# 780-00012-P1_rev4_Sch_M2_Focus_Drive.net
KiCad netlist of a schematic drawn in Altium Designer
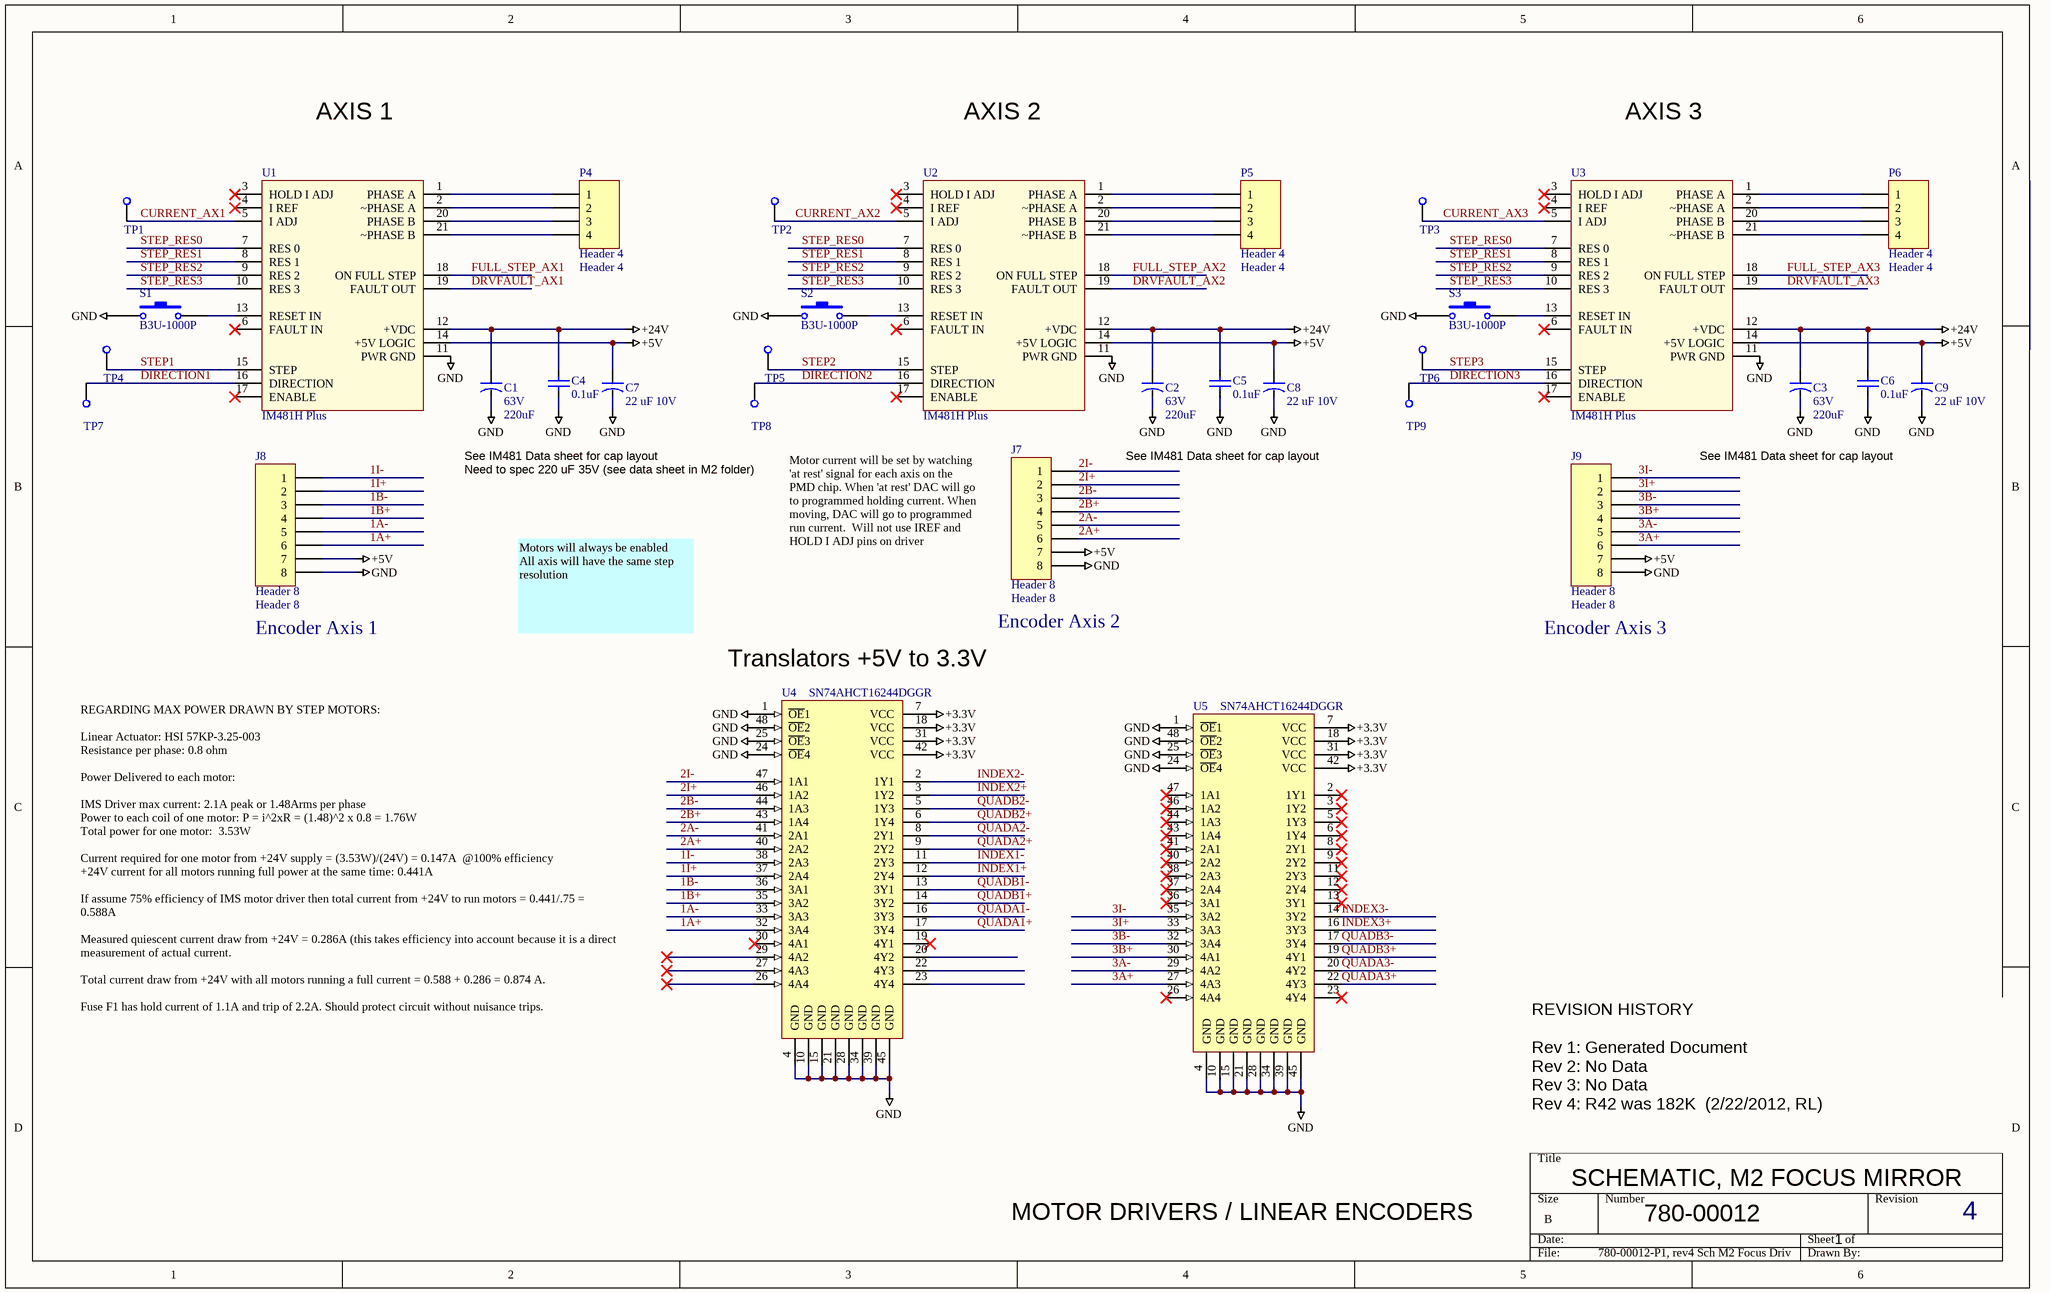
[diagram p0: 780-00012-P1, rev4 Sch M2 Focus Drive.SchDoc]

(export (version "E")
  (design (tool "Eeschema 10.0.6"))
  (components
    (comp (ref "C1")
      (value "63V")
      (footprint "CAP 220uF 63V")
      (description "CAP 220UF 63V ELECT MVH SMD")
      (fields (field (name "MANUFACTURER") "United Chemi-Con") (field (name "ALTIUM_VALUE") "220uF"))
      (libsource (lib "Richs Schematic Components") (part "Cap 220uF, 63V"))
    )
    (comp (ref "C2")
      (value "63V")
      (footprint "CAP 220uF 63V")
      (description "CAP 220UF 63V ELECT MVH SMD")
      (fields (field (name "MANUFACTURER") "United Chemi-Con") (field (name "ALTIUM_VALUE") "220uF"))
      (libsource (lib "Richs Schematic Components") (part "Cap 220uF, 63V"))
    )
    (comp (ref "C3")
      (value "63V")
      (footprint "CAP 220uF 63V")
      (description "CAP 220UF 63V ELECT MVH SMD")
      (fields (field (name "MANUFACTURER") "United Chemi-Con") (field (name "ALTIUM_VALUE") "220uF"))
      (libsource (lib "Richs Schematic Components") (part "Cap 220uF, 63V"))
    )
    (comp (ref "C4")
      (value "0.1uF")
      (footprint "SMD_0805")
      (description "Capacitor")
      (fields (field (name "Comment") "Cap SMD"))
      (libsource (lib "Richs Schematic Components") (part "Cap SMD"))
    )
    (comp (ref "C5")
      (value "0.1uF")
      (footprint "SMD_0805")
      (description "Capacitor")
      (fields (field (name "Comment") "Cap SMD"))
      (libsource (lib "Richs Schematic Components") (part "Cap SMD"))
    )
    (comp (ref "C6")
      (value "0.1uF")
      (footprint "SMD_0805")
      (description "Capacitor")
      (fields (field (name "Comment") "Cap SMD"))
      (libsource (lib "Richs Schematic Components") (part "Cap SMD"))
    )
    (comp (ref "C7")
      (value "22 uF 10V")
      (footprint "SMD_CAP_3216")
      (description "outline 3.2mm x 1.6mm")
      (fields (field (name "MANUFACTURER") "KEMET") (field (name "Comment") "16V"))
      (libsource (lib "Richs Schematic Components") (part "Cap Tant 16V"))
    )
    (comp (ref "C8")
      (value "22 uF 10V")
      (footprint "SMD_CAP_3216")
      (description "outline 3.2mm x 1.6mm")
      (fields (field (name "MANUFACTURER") "KEMET") (field (name "Comment") "16V"))
      (libsource (lib "Richs Schematic Components") (part "Cap Tant 16V"))
    )
    (comp (ref "C9")
      (value "22 uF 10V")
      (footprint "SMD_CAP_3216")
      (description "outline 3.2mm x 1.6mm")
      (fields (field (name "MANUFACTURER") "KEMET") (field (name "Comment") "16V"))
      (libsource (lib "Richs Schematic Components") (part "Cap Tant 16V"))
    )
    (comp (ref "J7")
      (value "Header 8")
      (footprint "HDR1X8 for IDC")
      (description "Header, 8-Pin")
      (fields (field (name "ALTIUM_VALUE") "Header 8"))
      (libsource (lib "Richs Schematic Components") (part "Header 8"))
    )
    (comp (ref "J8")
      (value "Header 8")
      (footprint "HDR1X8 for IDC")
      (description "Header, 8-Pin")
      (fields (field (name "ALTIUM_VALUE") "Header 8"))
      (libsource (lib "Richs Schematic Components") (part "Header 8"))
    )
    (comp (ref "J9")
      (value "Header 8")
      (footprint "HDR1X8 for IDC")
      (description "Header, 8-Pin")
      (fields (field (name "ALTIUM_VALUE") "Header 8"))
      (libsource (lib "Richs Schematic Components") (part "Header 8"))
    )
    (comp (ref "P4")
      (value "Header 4")
      (footprint "HDR1X4 for IDC")
      (description "Header, 4-Pin")
      (fields (field (name "ALTIUM_VALUE") "Header 4"))
      (libsource (lib "Richs Schematic Components") (part "Header 4"))
    )
    (comp (ref "P5")
      (value "Header 4")
      (footprint "HDR1X4 for IDC")
      (description "Header, 4-Pin")
      (fields (field (name "ALTIUM_VALUE") "Header 4"))
      (libsource (lib "Richs Schematic Components") (part "Header 4"))
    )
    (comp (ref "P6")
      (value "Header 4")
      (footprint "HDR1X4 for IDC")
      (description "Header, 4-Pin")
      (fields (field (name "ALTIUM_VALUE") "Header 4"))
      (libsource (lib "Richs Schematic Components") (part "Header 4"))
    )
    (comp (ref "S1")
      (value "B3U-1000P")
      (footprint "B3U-1000P")
      (description "Switch")
      (fields (field (name "MANUFACTURER") "Omron Electronics"))
      (libsource (lib "Miscellaneous Devices") (part "SW-PB"))
    )
    (comp (ref "S2")
      (value "B3U-1000P")
      (footprint "B3U-1000P")
      (description "Switch")
      (fields (field (name "MANUFACTURER") "Omron Electronics"))
      (libsource (lib "Miscellaneous Devices") (part "SW-PB"))
    )
    (comp (ref "S3")
      (value "B3U-1000P")
      (footprint "B3U-1000P")
      (description "Switch")
      (fields (field (name "MANUFACTURER") "Omron Electronics"))
      (libsource (lib "Miscellaneous Devices") (part "SW-PB"))
    )
    (comp (ref "TP1")
      (value "Test Point SMD")
      (footprint "SMD_TEST POINT")
      (description "SMD loop test point")
      (libsource (lib "Richs Schematic Components") (part "Test Point SMD"))
    )
    (comp (ref "TP2")
      (value "Test Point SMD")
      (footprint "SMD_TEST POINT")
      (description "SMD loop test point")
      (libsource (lib "Richs Schematic Components") (part "Test Point SMD"))
    )
    (comp (ref "TP3")
      (value "Test Point SMD")
      (footprint "SMD_TEST POINT")
      (description "SMD loop test point")
      (libsource (lib "Richs Schematic Components") (part "Test Point SMD"))
    )
    (comp (ref "TP4")
      (value "Test Point SMD")
      (footprint "SMD_TEST POINT")
      (description "SMD loop test point")
      (libsource (lib "Richs Schematic Components") (part "Test Point SMD"))
    )
    (comp (ref "TP5")
      (value "Test Point SMD")
      (footprint "SMD_TEST POINT")
      (description "SMD loop test point")
      (libsource (lib "Richs Schematic Components") (part "Test Point SMD"))
    )
    (comp (ref "TP6")
      (value "Test Point SMD")
      (footprint "SMD_TEST POINT")
      (description "SMD loop test point")
      (libsource (lib "Richs Schematic Components") (part "Test Point SMD"))
    )
    (comp (ref "TP7")
      (value "Test Point SMD")
      (footprint "SMD_TEST POINT")
      (description "SMD loop test point")
      (libsource (lib "Richs Schematic Components") (part "Test Point SMD"))
    )
    (comp (ref "TP8")
      (value "Test Point SMD")
      (footprint "SMD_TEST POINT")
      (description "SMD loop test point")
      (libsource (lib "Richs Schematic Components") (part "Test Point SMD"))
    )
    (comp (ref "TP9")
      (value "Test Point SMD")
      (footprint "SMD_TEST POINT")
      (description "SMD loop test point")
      (libsource (lib "Richs Schematic Components") (part "Test Point SMD"))
    )
    (comp (ref "U1")
      (value "IM481H Plus")
      (footprint "IM481H Vertical")
      (description "Hybrid stepper motor driver")
      (libsource (lib "Richs Schematic Components") (part "IM481H Plus"))
    )
    (comp (ref "U2")
      (value "IM481H Plus")
      (footprint "IM481H Vertical")
      (description "Hybrid stepper motor driver")
      (libsource (lib "Richs Schematic Components") (part "IM481H Plus"))
    )
    (comp (ref "U3")
      (value "IM481H Plus")
      (footprint "IM481H Vertical")
      (description "Hybrid stepper motor driver")
      (libsource (lib "Richs Schematic Components") (part "IM481H Plus"))
    )
    (comp (ref "U4")
      (value "SN74AHCT16244DGGR")
      (footprint "DGG048_N")
      (description "16-Bit Buffer/Driver with 3-State Outputs")
      (libsource (lib "TI Logic Buffer Line Driver") (part "SN74AHCT16244DGGR"))
    )
    (comp (ref "U5")
      (value "SN74AHCT16244DGGR")
      (footprint "DGG048_N")
      (description "16-Bit Buffer/Driver with 3-State Outputs")
      (libsource (lib "TI Logic Buffer Line Driver") (part "SN74AHCT16244DGGR"))
    )
  )
  (nets
    (net (code "1") (name "+3.3V") (class "Default")
      (node (ref "U4") (pin "18") (pinfunction "VCC_18") (pintype "power_in"))
      (node (ref "U4") (pin "31") (pinfunction "VCC_31") (pintype "power_in"))
      (node (ref "U4") (pin "42") (pinfunction "VCC_42") (pintype "power_in"))
      (node (ref "U4") (pin "7") (pinfunction "VCC_7") (pintype "power_in"))
      (node (ref "U5") (pin "18") (pinfunction "VCC_18") (pintype "power_in"))
      (node (ref "U5") (pin "31") (pinfunction "VCC_31") (pintype "power_in"))
      (node (ref "U5") (pin "42") (pinfunction "VCC_42") (pintype "power_in"))
      (node (ref "U5") (pin "7") (pinfunction "VCC_7") (pintype "power_in"))
    )
    (net (code "2") (name "+5V") (class "Default")
      (node (ref "C7") (pin "1") (pinfunction "1_1") (pintype "passive"))
      (node (ref "C8") (pin "1") (pinfunction "1_1") (pintype "passive"))
      (node (ref "C9") (pin "1") (pinfunction "1_1") (pintype "passive"))
      (node (ref "J7") (pin "7") (pinfunction "7_7") (pintype "passive"))
      (node (ref "J8") (pin "7") (pinfunction "7_7") (pintype "passive"))
      (node (ref "J9") (pin "7") (pinfunction "7_7") (pintype "passive"))
      (node (ref "U1") (pin "14") (pinfunction "+5V_LOGIC_14") (pintype "passive"))
      (node (ref "U2") (pin "14") (pinfunction "+5V_LOGIC_14") (pintype "passive"))
      (node (ref "U3") (pin "14") (pinfunction "+5V_LOGIC_14") (pintype "passive"))
    )
    (net (code "3") (name "+24V") (class "Default")
      (node (ref "C1") (pin "1") (pinfunction "1_1") (pintype "passive"))
      (node (ref "C2") (pin "1") (pinfunction "1_1") (pintype "passive"))
      (node (ref "C3") (pin "1") (pinfunction "1_1") (pintype "passive"))
      (node (ref "C4") (pin "2") (pinfunction "2_2") (pintype "passive"))
      (node (ref "C5") (pin "2") (pinfunction "2_2") (pintype "passive"))
      (node (ref "C6") (pin "2") (pinfunction "2_2") (pintype "passive"))
      (node (ref "U1") (pin "12") (pinfunction "+VDC_12") (pintype "passive"))
      (node (ref "U2") (pin "12") (pinfunction "+VDC_12") (pintype "passive"))
      (node (ref "U3") (pin "12") (pinfunction "+VDC_12") (pintype "passive"))
    )
    (net (code "4") (name "/1A+") (class "Default")
      (node (ref "J8") (pin "6") (pinfunction "6_6") (pintype "passive"))
      (node (ref "U4") (pin "32") (pinfunction "3A4_32") (pintype "input"))
    )
    (net (code "5") (name "/1A-") (class "Default")
      (node (ref "J8") (pin "5") (pinfunction "5_5") (pintype "passive"))
      (node (ref "U4") (pin "33") (pinfunction "3A3_33") (pintype "input"))
    )
    (net (code "6") (name "/1B+") (class "Default")
      (node (ref "J8") (pin "4") (pinfunction "4_4") (pintype "passive"))
      (node (ref "U4") (pin "35") (pinfunction "3A2_35") (pintype "input"))
    )
    (net (code "7") (name "/1B-") (class "Default")
      (node (ref "J8") (pin "3") (pinfunction "3_3") (pintype "passive"))
      (node (ref "U4") (pin "36") (pinfunction "3A1_36") (pintype "input"))
    )
    (net (code "8") (name "/1I+") (class "Default")
      (node (ref "J8") (pin "2") (pinfunction "2_2") (pintype "passive"))
      (node (ref "U4") (pin "37") (pinfunction "2A4_37") (pintype "input"))
    )
    (net (code "9") (name "/1I-") (class "Default")
      (node (ref "J8") (pin "1") (pinfunction "1_1") (pintype "passive"))
      (node (ref "U4") (pin "38") (pinfunction "2A3_38") (pintype "input"))
    )
    (net (code "10") (name "/2A+") (class "Default")
      (node (ref "J7") (pin "6") (pinfunction "6_6") (pintype "passive"))
      (node (ref "U4") (pin "40") (pinfunction "2A2_40") (pintype "input"))
    )
    (net (code "11") (name "/2A-") (class "Default")
      (node (ref "J7") (pin "5") (pinfunction "5_5") (pintype "passive"))
      (node (ref "U4") (pin "41") (pinfunction "2A1_41") (pintype "input"))
    )
    (net (code "12") (name "/2B+") (class "Default")
      (node (ref "J7") (pin "4") (pinfunction "4_4") (pintype "passive"))
      (node (ref "U4") (pin "43") (pinfunction "1A4_43") (pintype "input"))
    )
    (net (code "13") (name "/2B-") (class "Default")
      (node (ref "J7") (pin "3") (pinfunction "3_3") (pintype "passive"))
      (node (ref "U4") (pin "44") (pinfunction "1A3_44") (pintype "input"))
    )
    (net (code "14") (name "/2I+") (class "Default")
      (node (ref "J7") (pin "2") (pinfunction "2_2") (pintype "passive"))
      (node (ref "U4") (pin "46") (pinfunction "1A2_46") (pintype "input"))
    )
    (net (code "15") (name "/2I-") (class "Default")
      (node (ref "J7") (pin "1") (pinfunction "1_1") (pintype "passive"))
      (node (ref "U4") (pin "47") (pinfunction "1A1_47") (pintype "input"))
    )
    (net (code "16") (name "/3A+") (class "Default")
      (node (ref "J9") (pin "6") (pinfunction "6_6") (pintype "passive"))
      (node (ref "U5") (pin "27") (pinfunction "4A3_27") (pintype "input"))
    )
    (net (code "17") (name "/3A-") (class "Default")
      (node (ref "J9") (pin "5") (pinfunction "5_5") (pintype "passive"))
      (node (ref "U5") (pin "29") (pinfunction "4A2_29") (pintype "input"))
    )
    (net (code "18") (name "/3B+") (class "Default")
      (node (ref "J9") (pin "4") (pinfunction "4_4") (pintype "passive"))
      (node (ref "U5") (pin "30") (pinfunction "4A1_30") (pintype "input"))
    )
    (net (code "19") (name "/3B-") (class "Default")
      (node (ref "J9") (pin "3") (pinfunction "3_3") (pintype "passive"))
      (node (ref "U5") (pin "32") (pinfunction "3A4_32") (pintype "input"))
    )
    (net (code "20") (name "/3I+") (class "Default")
      (node (ref "J9") (pin "2") (pinfunction "2_2") (pintype "passive"))
      (node (ref "U5") (pin "33") (pinfunction "3A3_33") (pintype "input"))
    )
    (net (code "21") (name "/3I-") (class "Default")
      (node (ref "J9") (pin "1") (pinfunction "1_1") (pintype "passive"))
      (node (ref "U5") (pin "35") (pinfunction "3A2_35") (pintype "input"))
    )
    (net (code "22") (name "/CURRENT_AX1") (class "Default")
      (node (ref "TP1") (pin "1") (pinfunction "TP_1") (pintype "passive"))
      (node (ref "U1") (pin "5") (pinfunction "I_ADJ_5") (pintype "passive"))
    )
    (net (code "23") (name "/CURRENT_AX2") (class "Default")
      (node (ref "TP2") (pin "1") (pinfunction "TP_1") (pintype "passive"))
      (node (ref "U2") (pin "5") (pinfunction "I_ADJ_5") (pintype "passive"))
    )
    (net (code "24") (name "/CURRENT_AX3") (class "Default")
      (node (ref "TP3") (pin "1") (pinfunction "TP_1") (pintype "passive"))
      (node (ref "U3") (pin "5") (pinfunction "I_ADJ_5") (pintype "passive"))
    )
    (net (code "25") (name "/DIRECTION1") (class "Default")
      (node (ref "TP7") (pin "1") (pinfunction "TP_1") (pintype "passive"))
      (node (ref "U1") (pin "16") (pinfunction "DIRECTION_16") (pintype "passive"))
    )
    (net (code "26") (name "/DIRECTION2") (class "Default")
      (node (ref "TP8") (pin "1") (pinfunction "TP_1") (pintype "passive"))
      (node (ref "U2") (pin "16") (pinfunction "DIRECTION_16") (pintype "passive"))
    )
    (net (code "27") (name "/DIRECTION3") (class "Default")
      (node (ref "TP9") (pin "1") (pinfunction "TP_1") (pintype "passive"))
      (node (ref "U3") (pin "16") (pinfunction "DIRECTION_16") (pintype "passive"))
    )
    (net (code "28") (name "/DRVFAULT_AX1") (class "Default")
      (node (ref "U1") (pin "19") (pinfunction "FAULT_OUT_19") (pintype "passive"))
    )
    (net (code "29") (name "/DRVFAULT_AX2") (class "Default")
      (node (ref "U2") (pin "19") (pinfunction "FAULT_OUT_19") (pintype "passive"))
    )
    (net (code "30") (name "/DRVFAULT_AX3") (class "Default")
      (node (ref "U3") (pin "19") (pinfunction "FAULT_OUT_19") (pintype "passive"))
    )
    (net (code "31") (name "/FULL_STEP_AX1") (class "Default")
      (node (ref "U1") (pin "18") (pinfunction "ON_FULL_STEP_18") (pintype "passive"))
    )
    (net (code "32") (name "/FULL_STEP_AX2") (class "Default")
      (node (ref "U2") (pin "18") (pinfunction "ON_FULL_STEP_18") (pintype "passive"))
    )
    (net (code "33") (name "/FULL_STEP_AX3") (class "Default")
      (node (ref "U3") (pin "18") (pinfunction "ON_FULL_STEP_18") (pintype "passive"))
    )
    (net (code "34") (name "/INDEX1+") (class "Default")
      (node (ref "U4") (pin "12") (pinfunction "2Y4_12") (pintype "tri_state"))
    )
    (net (code "35") (name "/INDEX1-") (class "Default")
      (node (ref "U4") (pin "11") (pinfunction "2Y3_11") (pintype "tri_state"))
    )
    (net (code "36") (name "/INDEX2+") (class "Default")
      (node (ref "U4") (pin "3") (pinfunction "1Y2_3") (pintype "tri_state"))
    )
    (net (code "37") (name "/INDEX2-") (class "Default")
      (node (ref "U4") (pin "2") (pinfunction "1Y1_2") (pintype "tri_state"))
    )
    (net (code "38") (name "/INDEX3+") (class "Default")
      (node (ref "U5") (pin "16") (pinfunction "3Y3_16") (pintype "tri_state"))
    )
    (net (code "39") (name "/INDEX3-") (class "Default")
      (node (ref "U5") (pin "14") (pinfunction "3Y2_14") (pintype "tri_state"))
    )
    (net (code "40") (name "/QUADA1+") (class "Default")
      (node (ref "U4") (pin "17") (pinfunction "3Y4_17") (pintype "tri_state"))
    )
    (net (code "41") (name "/QUADA1-") (class "Default")
      (node (ref "U4") (pin "16") (pinfunction "3Y3_16") (pintype "tri_state"))
    )
    (net (code "42") (name "/QUADA2+") (class "Default")
      (node (ref "U4") (pin "9") (pinfunction "2Y2_9") (pintype "tri_state"))
    )
    (net (code "43") (name "/QUADA2-") (class "Default")
      (node (ref "U4") (pin "8") (pinfunction "2Y1_8") (pintype "tri_state"))
    )
    (net (code "44") (name "/QUADA3+") (class "Default")
      (node (ref "U5") (pin "22") (pinfunction "4Y3_22") (pintype "tri_state"))
    )
    (net (code "45") (name "/QUADA3-") (class "Default")
      (node (ref "U5") (pin "20") (pinfunction "4Y2_20") (pintype "tri_state"))
    )
    (net (code "46") (name "/QUADB1+") (class "Default")
      (node (ref "U4") (pin "14") (pinfunction "3Y2_14") (pintype "tri_state"))
    )
    (net (code "47") (name "/QUADB1-") (class "Default")
      (node (ref "U4") (pin "13") (pinfunction "3Y1_13") (pintype "tri_state"))
    )
    (net (code "48") (name "/QUADB2+") (class "Default")
      (node (ref "U4") (pin "6") (pinfunction "1Y4_6") (pintype "tri_state"))
    )
    (net (code "49") (name "/QUADB2-") (class "Default")
      (node (ref "U4") (pin "5") (pinfunction "1Y3_5") (pintype "tri_state"))
    )
    (net (code "50") (name "/QUADB3+") (class "Default")
      (node (ref "U5") (pin "19") (pinfunction "4Y1_19") (pintype "tri_state"))
    )
    (net (code "51") (name "/QUADB3-") (class "Default")
      (node (ref "U5") (pin "17") (pinfunction "3Y4_17") (pintype "tri_state"))
    )
    (net (code "52") (name "/STEP1") (class "Default")
      (node (ref "TP4") (pin "1") (pinfunction "TP_1") (pintype "passive"))
      (node (ref "U1") (pin "15") (pinfunction "STEP_15") (pintype "passive"))
    )
    (net (code "53") (name "/STEP2") (class "Default")
      (node (ref "TP5") (pin "1") (pinfunction "TP_1") (pintype "passive"))
      (node (ref "U2") (pin "15") (pinfunction "STEP_15") (pintype "passive"))
    )
    (net (code "54") (name "/STEP3") (class "Default")
      (node (ref "TP6") (pin "1") (pinfunction "TP_1") (pintype "passive"))
      (node (ref "U3") (pin "15") (pinfunction "STEP_15") (pintype "passive"))
    )
    (net (code "55") (name "/STEP_RES0") (class "Default")
      (node (ref "U1") (pin "7") (pinfunction "RES_0_7") (pintype "passive"))
      (node (ref "U2") (pin "7") (pinfunction "RES_0_7") (pintype "passive"))
      (node (ref "U3") (pin "7") (pinfunction "RES_0_7") (pintype "passive"))
    )
    (net (code "56") (name "/STEP_RES1") (class "Default")
      (node (ref "U1") (pin "8") (pinfunction "RES_1_8") (pintype "passive"))
      (node (ref "U2") (pin "8") (pinfunction "RES_1_8") (pintype "passive"))
      (node (ref "U3") (pin "8") (pinfunction "RES_1_8") (pintype "passive"))
    )
    (net (code "57") (name "/STEP_RES2") (class "Default")
      (node (ref "U1") (pin "9") (pinfunction "RES_2_9") (pintype "passive"))
      (node (ref "U2") (pin "9") (pinfunction "RES_2_9") (pintype "passive"))
      (node (ref "U3") (pin "9") (pinfunction "RES_2_9") (pintype "passive"))
    )
    (net (code "58") (name "/STEP_RES3") (class "Default")
      (node (ref "U1") (pin "10") (pinfunction "RES_3_10") (pintype "passive"))
      (node (ref "U2") (pin "10") (pinfunction "RES_3_10") (pintype "passive"))
      (node (ref "U3") (pin "10") (pinfunction "RES_3_10") (pintype "passive"))
    )
    (net (code "59") (name "GND") (class "Default")
      (node (ref "C1") (pin "2") (pinfunction "2_2") (pintype "passive"))
      (node (ref "C2") (pin "2") (pinfunction "2_2") (pintype "passive"))
      (node (ref "C3") (pin "2") (pinfunction "2_2") (pintype "passive"))
      (node (ref "C4") (pin "1") (pinfunction "1_1") (pintype "passive"))
      (node (ref "C5") (pin "1") (pinfunction "1_1") (pintype "passive"))
      (node (ref "C6") (pin "1") (pinfunction "1_1") (pintype "passive"))
      (node (ref "C7") (pin "2") (pinfunction "2_2") (pintype "passive"))
      (node (ref "C8") (pin "2") (pinfunction "2_2") (pintype "passive"))
      (node (ref "C9") (pin "2") (pinfunction "2_2") (pintype "passive"))
      (node (ref "J7") (pin "8") (pinfunction "8_8") (pintype "passive"))
      (node (ref "J8") (pin "8") (pinfunction "8_8") (pintype "passive"))
      (node (ref "J9") (pin "8") (pinfunction "8_8") (pintype "passive"))
      (node (ref "S1") (pin "1") (pinfunction "1_1") (pintype "passive"))
      (node (ref "S2") (pin "1") (pinfunction "1_1") (pintype "passive"))
      (node (ref "S3") (pin "1") (pinfunction "1_1") (pintype "passive"))
      (node (ref "U1") (pin "11") (pinfunction "PWR_GND_11") (pintype "passive"))
      (node (ref "U2") (pin "11") (pinfunction "PWR_GND_11") (pintype "passive"))
      (node (ref "U3") (pin "11") (pinfunction "PWR_GND_11") (pintype "passive"))
      (node (ref "U4") (pin "1") (pinfunction "~{OE}1_1") (pintype "input"))
      (node (ref "U4") (pin "10") (pinfunction "GND_10") (pintype "power_in"))
      (node (ref "U4") (pin "15") (pinfunction "GND_15") (pintype "power_in"))
      (node (ref "U4") (pin "21") (pinfunction "GND_21") (pintype "power_in"))
      (node (ref "U4") (pin "24") (pinfunction "~{OE}4_24") (pintype "input"))
      (node (ref "U4") (pin "25") (pinfunction "~{OE}3_25") (pintype "input"))
      (node (ref "U4") (pin "28") (pinfunction "GND_28") (pintype "power_in"))
      (node (ref "U4") (pin "34") (pinfunction "GND_34") (pintype "power_in"))
      (node (ref "U4") (pin "39") (pinfunction "GND_39") (pintype "power_in"))
      (node (ref "U4") (pin "4") (pinfunction "GND_4") (pintype "power_in"))
      (node (ref "U4") (pin "45") (pinfunction "GND_45") (pintype "power_in"))
      (node (ref "U4") (pin "48") (pinfunction "~{OE}2_48") (pintype "input"))
      (node (ref "U5") (pin "1") (pinfunction "~{OE}1_1") (pintype "input"))
      (node (ref "U5") (pin "10") (pinfunction "GND_10") (pintype "power_in"))
      (node (ref "U5") (pin "15") (pinfunction "GND_15") (pintype "power_in"))
      (node (ref "U5") (pin "21") (pinfunction "GND_21") (pintype "power_in"))
      (node (ref "U5") (pin "24") (pinfunction "~{OE}4_24") (pintype "input"))
      (node (ref "U5") (pin "25") (pinfunction "~{OE}3_25") (pintype "input"))
      (node (ref "U5") (pin "28") (pinfunction "GND_28") (pintype "power_in"))
      (node (ref "U5") (pin "34") (pinfunction "GND_34") (pintype "power_in"))
      (node (ref "U5") (pin "39") (pinfunction "GND_39") (pintype "power_in"))
      (node (ref "U5") (pin "4") (pinfunction "GND_4") (pintype "power_in"))
      (node (ref "U5") (pin "45") (pinfunction "GND_45") (pintype "power_in"))
      (node (ref "U5") (pin "48") (pinfunction "~{OE}2_48") (pintype "input"))
    )
    (net (code "60") (name "Net-(U1-PHASE_A)") (class "Default")
      (node (ref "P4") (pin "1") (pinfunction "1_1") (pintype "passive"))
      (node (ref "U1") (pin "1") (pinfunction "PHASE_A_1") (pintype "passive"))
    )
    (net (code "61") (name "Net-(U1-PHASE_B)") (class "Default")
      (node (ref "P4") (pin "3") (pinfunction "3_3") (pintype "passive"))
      (node (ref "U1") (pin "20") (pinfunction "PHASE_B_20") (pintype "passive"))
    )
    (net (code "62") (name "Net-(U1-RESET_IN)") (class "Default")
      (node (ref "S1") (pin "2") (pinfunction "2_2") (pintype "passive"))
      (node (ref "U1") (pin "13") (pinfunction "RESET_IN_13") (pintype "passive"))
    )
    (net (code "63") (name "Net-(U1-~PHASE_A)") (class "Default")
      (node (ref "P4") (pin "2") (pinfunction "2_2") (pintype "passive"))
      (node (ref "U1") (pin "2") (pinfunction "~PHASE_A_2") (pintype "passive"))
    )
    (net (code "64") (name "Net-(U1-~PHASE_B)") (class "Default")
      (node (ref "P4") (pin "4") (pinfunction "4_4") (pintype "passive"))
      (node (ref "U1") (pin "21") (pinfunction "~PHASE_B_21") (pintype "passive"))
    )
    (net (code "65") (name "Net-(U2-PHASE_A)") (class "Default")
      (node (ref "P5") (pin "1") (pinfunction "1_1") (pintype "passive"))
      (node (ref "U2") (pin "1") (pinfunction "PHASE_A_1") (pintype "passive"))
    )
    (net (code "66") (name "Net-(U2-PHASE_B)") (class "Default")
      (node (ref "P5") (pin "3") (pinfunction "3_3") (pintype "passive"))
      (node (ref "U2") (pin "20") (pinfunction "PHASE_B_20") (pintype "passive"))
    )
    (net (code "67") (name "Net-(U2-RESET_IN)") (class "Default")
      (node (ref "S2") (pin "2") (pinfunction "2_2") (pintype "passive"))
      (node (ref "U2") (pin "13") (pinfunction "RESET_IN_13") (pintype "passive"))
    )
    (net (code "68") (name "Net-(U2-~PHASE_A)") (class "Default")
      (node (ref "P5") (pin "2") (pinfunction "2_2") (pintype "passive"))
      (node (ref "U2") (pin "2") (pinfunction "~PHASE_A_2") (pintype "passive"))
    )
    (net (code "69") (name "Net-(U2-~PHASE_B)") (class "Default")
      (node (ref "P5") (pin "4") (pinfunction "4_4") (pintype "passive"))
      (node (ref "U2") (pin "21") (pinfunction "~PHASE_B_21") (pintype "passive"))
    )
    (net (code "70") (name "Net-(U3-PHASE_A)") (class "Default")
      (node (ref "P6") (pin "1") (pinfunction "1_1") (pintype "passive"))
      (node (ref "U3") (pin "1") (pinfunction "PHASE_A_1") (pintype "passive"))
    )
    (net (code "71") (name "Net-(U3-PHASE_B)") (class "Default")
      (node (ref "P6") (pin "3") (pinfunction "3_3") (pintype "passive"))
      (node (ref "U3") (pin "20") (pinfunction "PHASE_B_20") (pintype "passive"))
    )
    (net (code "72") (name "Net-(U3-RESET_IN)") (class "Default")
      (node (ref "S3") (pin "2") (pinfunction "2_2") (pintype "passive"))
      (node (ref "U3") (pin "13") (pinfunction "RESET_IN_13") (pintype "passive"))
    )
    (net (code "73") (name "Net-(U3-~PHASE_A)") (class "Default")
      (node (ref "P6") (pin "2") (pinfunction "2_2") (pintype "passive"))
      (node (ref "U3") (pin "2") (pinfunction "~PHASE_A_2") (pintype "passive"))
    )
    (net (code "74") (name "Net-(U3-~PHASE_B)") (class "Default")
      (node (ref "P6") (pin "4") (pinfunction "4_4") (pintype "passive"))
      (node (ref "U3") (pin "21") (pinfunction "~PHASE_B_21") (pintype "passive"))
    )
    (net (code "75") (name "unconnected-(U1-ENABLE-Pad17)") (class "Default")
      (node (ref "U1") (pin "17") (pinfunction "ENABLE_17") (pintype "passive+no_connect"))
    )
    (net (code "76") (name "unconnected-(U1-FAULT_IN-Pad6)") (class "Default")
      (node (ref "U1") (pin "6") (pinfunction "FAULT_IN_6") (pintype "passive+no_connect"))
    )
    (net (code "77") (name "unconnected-(U1-HOLD_I_ADJ-Pad3)") (class "Default")
      (node (ref "U1") (pin "3") (pinfunction "HOLD_I_ADJ_3") (pintype "passive+no_connect"))
    )
    (net (code "78") (name "unconnected-(U1-I_REF-Pad4)") (class "Default")
      (node (ref "U1") (pin "4") (pinfunction "I_REF_4") (pintype "passive+no_connect"))
    )
    (net (code "79") (name "unconnected-(U2-ENABLE-Pad17)") (class "Default")
      (node (ref "U2") (pin "17") (pinfunction "ENABLE_17") (pintype "passive+no_connect"))
    )
    (net (code "80") (name "unconnected-(U2-FAULT_IN-Pad6)") (class "Default")
      (node (ref "U2") (pin "6") (pinfunction "FAULT_IN_6") (pintype "passive+no_connect"))
    )
    (net (code "81") (name "unconnected-(U2-HOLD_I_ADJ-Pad3)") (class "Default")
      (node (ref "U2") (pin "3") (pinfunction "HOLD_I_ADJ_3") (pintype "passive+no_connect"))
    )
    (net (code "82") (name "unconnected-(U2-I_REF-Pad4)") (class "Default")
      (node (ref "U2") (pin "4") (pinfunction "I_REF_4") (pintype "passive+no_connect"))
    )
    (net (code "83") (name "unconnected-(U3-ENABLE-Pad17)") (class "Default")
      (node (ref "U3") (pin "17") (pinfunction "ENABLE_17") (pintype "passive+no_connect"))
    )
    (net (code "84") (name "unconnected-(U3-FAULT_IN-Pad6)") (class "Default")
      (node (ref "U3") (pin "6") (pinfunction "FAULT_IN_6") (pintype "passive+no_connect"))
    )
    (net (code "85") (name "unconnected-(U3-HOLD_I_ADJ-Pad3)") (class "Default")
      (node (ref "U3") (pin "3") (pinfunction "HOLD_I_ADJ_3") (pintype "passive+no_connect"))
    )
    (net (code "86") (name "unconnected-(U3-I_REF-Pad4)") (class "Default")
      (node (ref "U3") (pin "4") (pinfunction "I_REF_4") (pintype "passive+no_connect"))
    )
    (net (code "87") (name "unconnected-(U4-4A1-Pad30)") (class "Default")
      (node (ref "U4") (pin "30") (pinfunction "4A1_30") (pintype "input+no_connect"))
    )
    (net (code "88") (name "unconnected-(U4-4A2-Pad29)") (class "Default")
      (node (ref "U4") (pin "29") (pinfunction "4A2_29") (pintype "input+no_connect"))
    )
    (net (code "89") (name "unconnected-(U4-4A3-Pad27)") (class "Default")
      (node (ref "U4") (pin "27") (pinfunction "4A3_27") (pintype "input+no_connect"))
    )
    (net (code "90") (name "unconnected-(U4-4A4-Pad26)") (class "Default")
      (node (ref "U4") (pin "26") (pinfunction "4A4_26") (pintype "input+no_connect"))
    )
    (net (code "91") (name "unconnected-(U4-4Y1-Pad19)") (class "Default")
      (node (ref "U4") (pin "19") (pinfunction "4Y1_19") (pintype "tri_state+no_connect"))
    )
    (net (code "92") (name "unconnected-(U4-4Y2-Pad20)") (class "Default")
      (node (ref "U4") (pin "20") (pinfunction "4Y2_20") (pintype "tri_state"))
    )
    (net (code "93") (name "unconnected-(U4-4Y3-Pad22)") (class "Default")
      (node (ref "U4") (pin "22") (pinfunction "4Y3_22") (pintype "tri_state"))
    )
    (net (code "94") (name "unconnected-(U4-4Y4-Pad23)") (class "Default")
      (node (ref "U4") (pin "23") (pinfunction "4Y4_23") (pintype "tri_state"))
    )
    (net (code "95") (name "unconnected-(U5-1A1-Pad47)") (class "Default")
      (node (ref "U5") (pin "47") (pinfunction "1A1_47") (pintype "input+no_connect"))
    )
    (net (code "96") (name "unconnected-(U5-1A2-Pad46)") (class "Default")
      (node (ref "U5") (pin "46") (pinfunction "1A2_46") (pintype "input+no_connect"))
    )
    (net (code "97") (name "unconnected-(U5-1A3-Pad44)") (class "Default")
      (node (ref "U5") (pin "44") (pinfunction "1A3_44") (pintype "input+no_connect"))
    )
    (net (code "98") (name "unconnected-(U5-1A4-Pad43)") (class "Default")
      (node (ref "U5") (pin "43") (pinfunction "1A4_43") (pintype "input+no_connect"))
    )
    (net (code "99") (name "unconnected-(U5-1Y1-Pad2)") (class "Default")
      (node (ref "U5") (pin "2") (pinfunction "1Y1_2") (pintype "tri_state+no_connect"))
    )
    (net (code "100") (name "unconnected-(U5-1Y2-Pad3)") (class "Default")
      (node (ref "U5") (pin "3") (pinfunction "1Y2_3") (pintype "tri_state+no_connect"))
    )
    (net (code "101") (name "unconnected-(U5-1Y3-Pad5)") (class "Default")
      (node (ref "U5") (pin "5") (pinfunction "1Y3_5") (pintype "tri_state+no_connect"))
    )
    (net (code "102") (name "unconnected-(U5-1Y4-Pad6)") (class "Default")
      (node (ref "U5") (pin "6") (pinfunction "1Y4_6") (pintype "tri_state+no_connect"))
    )
    (net (code "103") (name "unconnected-(U5-2A1-Pad41)") (class "Default")
      (node (ref "U5") (pin "41") (pinfunction "2A1_41") (pintype "input+no_connect"))
    )
    (net (code "104") (name "unconnected-(U5-2A2-Pad40)") (class "Default")
      (node (ref "U5") (pin "40") (pinfunction "2A2_40") (pintype "input+no_connect"))
    )
    (net (code "105") (name "unconnected-(U5-2A3-Pad38)") (class "Default")
      (node (ref "U5") (pin "38") (pinfunction "2A3_38") (pintype "input+no_connect"))
    )
    (net (code "106") (name "unconnected-(U5-2A4-Pad37)") (class "Default")
      (node (ref "U5") (pin "37") (pinfunction "2A4_37") (pintype "input+no_connect"))
    )
    (net (code "107") (name "unconnected-(U5-2Y1-Pad8)") (class "Default")
      (node (ref "U5") (pin "8") (pinfunction "2Y1_8") (pintype "tri_state+no_connect"))
    )
    (net (code "108") (name "unconnected-(U5-2Y2-Pad9)") (class "Default")
      (node (ref "U5") (pin "9") (pinfunction "2Y2_9") (pintype "tri_state+no_connect"))
    )
    (net (code "109") (name "unconnected-(U5-2Y3-Pad11)") (class "Default")
      (node (ref "U5") (pin "11") (pinfunction "2Y3_11") (pintype "tri_state+no_connect"))
    )
    (net (code "110") (name "unconnected-(U5-2Y4-Pad12)") (class "Default")
      (node (ref "U5") (pin "12") (pinfunction "2Y4_12") (pintype "tri_state+no_connect"))
    )
    (net (code "111") (name "unconnected-(U5-3A1-Pad36)") (class "Default")
      (node (ref "U5") (pin "36") (pinfunction "3A1_36") (pintype "input+no_connect"))
    )
    (net (code "112") (name "unconnected-(U5-3Y1-Pad13)") (class "Default")
      (node (ref "U5") (pin "13") (pinfunction "3Y1_13") (pintype "tri_state+no_connect"))
    )
    (net (code "113") (name "unconnected-(U5-4A4-Pad26)") (class "Default")
      (node (ref "U5") (pin "26") (pinfunction "4A4_26") (pintype "input+no_connect"))
    )
    (net (code "114") (name "unconnected-(U5-4Y4-Pad23)") (class "Default")
      (node (ref "U5") (pin "23") (pinfunction "4Y4_23") (pintype "tri_state+no_connect"))
    )
  )
)
